# sensor.net
KiCad netlist of a schematic drawn in EAGLE
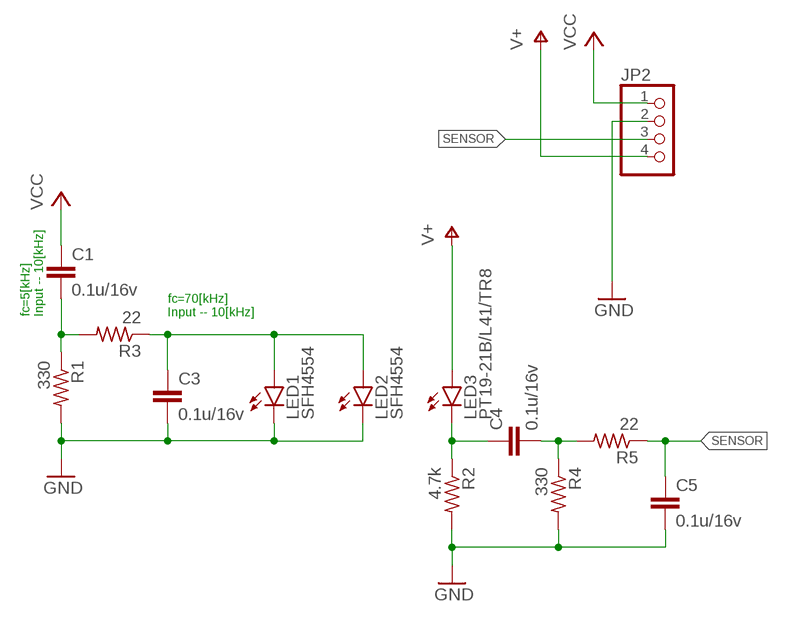
[diagram p0: schematic, sheet 1]

(export (version "E")
  (design (tool "Eeschema 10.0.6"))
  (components
    (comp (ref "C1")
      (value "0.1u/16v")
      (footprint "eagle-import:C0603")
      (libsource (lib "eagle-import") (part "C-EUC0603"))
    )
    (comp (ref "C3")
      (value "0.1u/16v")
      (footprint "eagle-import:C0603")
      (libsource (lib "eagle-import") (part "C-EUC0603"))
    )
    (comp (ref "C4")
      (value "0.1u/16v")
      (footprint "eagle-import:C0603")
      (libsource (lib "eagle-import") (part "C-EUC0603"))
    )
    (comp (ref "C5")
      (value "0.1u/16v")
      (footprint "eagle-import:C0603")
      (libsource (lib "eagle-import") (part "C-EUC0603"))
    )
    (comp (ref "JP2")
      (value "PINHD-1X4/90")
      (footprint "eagle-import:1X04_90")
      (libsource (lib "eagle-import") (part "PINHD-1X4/90"))
    )
    (comp (ref "LED1")
      (value "SFH4554")
      (footprint "eagle-import:LED5MM")
      (libsource (lib "eagle-import") (part "LED5MM"))
    )
    (comp (ref "LED2")
      (value "SFH4554")
      (footprint "eagle-import:LED5MM")
      (libsource (lib "eagle-import") (part "LED5MM"))
    )
    (comp (ref "LED3")
      (value "PT19-21B/L41/TR8")
      (footprint "eagle-import:SML0603")
      (libsource (lib "eagle-import") (part "LEDSML0603"))
    )
    (comp (ref "R1")
      (value "330")
      (footprint "eagle-import:R0603")
      (libsource (lib "eagle-import") (part "R-US_R0603"))
    )
    (comp (ref "R2")
      (value "4.7k")
      (footprint "eagle-import:R0603")
      (libsource (lib "eagle-import") (part "R-US_R0603"))
    )
    (comp (ref "R3")
      (value "22")
      (footprint "eagle-import:R0603")
      (libsource (lib "eagle-import") (part "R-US_R0603"))
    )
    (comp (ref "R4")
      (value "330")
      (footprint "eagle-import:R0603")
      (libsource (lib "eagle-import") (part "R-US_R0603"))
    )
    (comp (ref "R5")
      (value "22")
      (footprint "eagle-import:R0603")
      (libsource (lib "eagle-import") (part "R-US_R0603"))
    )
  )
  (nets
    (net (code "1") (name "GND") (class "Default")
      (node (ref "C3") (pin "2") (pinfunction "2_2") (pintype "passive"))
      (node (ref "C5") (pin "2") (pinfunction "2_2") (pintype "passive"))
      (node (ref "JP2") (pin "2") (pinfunction "2_2") (pintype "passive"))
      (node (ref "LED1") (pin "K") (pinfunction "C_K") (pintype "passive"))
      (node (ref "LED2") (pin "K") (pinfunction "C_K") (pintype "passive"))
      (node (ref "R1") (pin "2") (pinfunction "2_2") (pintype "passive"))
      (node (ref "R2") (pin "2") (pinfunction "2_2") (pintype "passive"))
      (node (ref "R4") (pin "2") (pinfunction "2_2") (pintype "passive"))
    )
    (net (code "2") (name "Net-(C1-Pad2)") (class "Default")
      (node (ref "C1") (pin "2") (pinfunction "2_2") (pintype "passive"))
      (node (ref "R1") (pin "1") (pinfunction "1_1") (pintype "passive"))
      (node (ref "R3") (pin "2") (pinfunction "2_2") (pintype "passive"))
    )
    (net (code "3") (name "Net-(C3-Pad1)") (class "Default")
      (node (ref "C3") (pin "1") (pinfunction "1_1") (pintype "passive"))
      (node (ref "LED1") (pin "A") (pinfunction "A_A") (pintype "passive"))
      (node (ref "LED2") (pin "A") (pinfunction "A_A") (pintype "passive"))
      (node (ref "R3") (pin "1") (pinfunction "1_1") (pintype "passive"))
    )
    (net (code "4") (name "Net-(C4-Pad1)") (class "Default")
      (node (ref "C4") (pin "1") (pinfunction "1_1") (pintype "passive"))
      (node (ref "LED3") (pin "C") (pinfunction "C_C") (pintype "passive"))
      (node (ref "R2") (pin "1") (pinfunction "1_1") (pintype "passive"))
    )
    (net (code "5") (name "Net-(C4-Pad2)") (class "Default")
      (node (ref "C4") (pin "2") (pinfunction "2_2") (pintype "passive"))
      (node (ref "R4") (pin "1") (pinfunction "1_1") (pintype "passive"))
      (node (ref "R5") (pin "2") (pinfunction "2_2") (pintype "passive"))
    )
    (net (code "6") (name "SENSOR") (class "Default")
      (node (ref "C5") (pin "1") (pinfunction "1_1") (pintype "passive"))
      (node (ref "JP2") (pin "3") (pinfunction "3_3") (pintype "passive"))
      (node (ref "R5") (pin "1") (pinfunction "1_1") (pintype "passive"))
    )
    (net (code "7") (name "V+") (class "Default")
      (node (ref "JP2") (pin "4") (pinfunction "4_4") (pintype "passive"))
      (node (ref "LED3") (pin "A") (pinfunction "A_A") (pintype "passive"))
    )
    (net (code "8") (name "VCC") (class "Default")
      (node (ref "C1") (pin "1") (pinfunction "1_1") (pintype "passive"))
      (node (ref "JP2") (pin "1") (pinfunction "1_1") (pintype "passive"))
    )
  )
)
